# obc_flash.net
KiCad netlist of a schematic drawn in Altium Designer
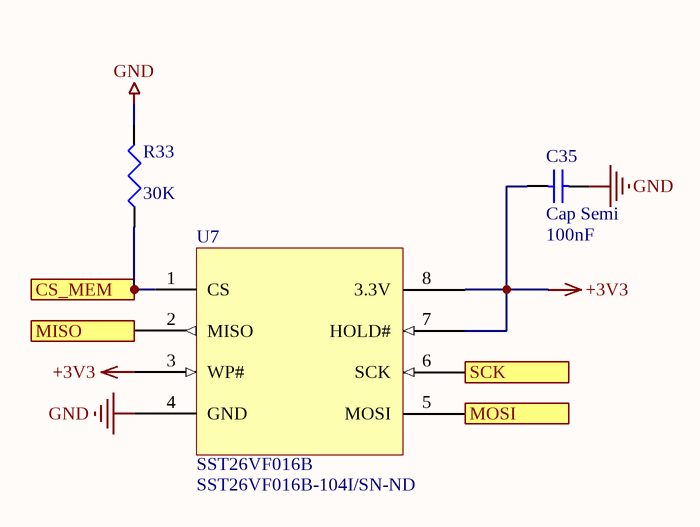
[diagram p0: obc_flash.SchDoc]

(export (version "E")
  (design (tool "Eeschema 10.0.6"))
  (components
    (comp (ref "C35")
      (value "Cap Semi")
      (footprint "1608[0603]")
      (description "Capacitor (Semiconductor SIM Model)")
      (fields (field (name "ALTIUM_VALUE") "100nF") (field (name "PUBLISHER") "Altium Limited"))
      (libsource (lib "Miscellaneous Devices") (part "Cap Semi"))
    )
    (comp (ref "R33")
      (value "30K")
      (footprint "J1-0603")
      (description "30K Pull-up resistor for RST. See page")
      (fields (field (name "PUBLISHER") "Altium Limited"))
      (libsource (lib "Miscellaneous Devices") (part "Res3"))
    )
    (comp (ref "U7")
      (value "SST26VF016B")
      (footprint "SOIC127P500X600-8N")
      (description "2.5V/3.0V 16 Mbit Serial Quad I/O (SQI) Flash Memory")
      (fields (field (name "SUPPLIER PART NUMBER 1") "SST26VF016B-104I/SN-ND"))
      (libsource (lib "heron-general") (part "SST26VF016B"))
    )
  )
  (nets
    (net (code "1") (name "+3V3") (class "Default")
      (node (ref "C35") (pin "1") (pinfunction "1_1") (pintype "passive"))
      (node (ref "U7") (pin "3") (pinfunction "WP#_3") (pintype "input"))
      (node (ref "U7") (pin "7") (pinfunction "HOLD#_7") (pintype "input"))
      (node (ref "U7") (pin "8") (pinfunction "3.3V_8") (pintype "power_in"))
    )
    (net (code "2") (name "/CS_MEM") (class "Default")
      (node (ref "R33") (pin "1") (pinfunction "1_1") (pintype "passive"))
      (node (ref "U7") (pin "1") (pinfunction "CS_1") (pintype "passive"))
    )
    (net (code "3") (name "/MISO") (class "Default")
      (node (ref "U7") (pin "2") (pinfunction "MISO_2") (pintype "output"))
    )
    (net (code "4") (name "/MOSI") (class "Default")
      (node (ref "U7") (pin "5") (pinfunction "MOSI_5") (pintype "passive"))
    )
    (net (code "5") (name "/SCK") (class "Default")
      (node (ref "U7") (pin "6") (pinfunction "SCK_6") (pintype "input"))
    )
    (net (code "6") (name "GND") (class "Default")
      (node (ref "C35") (pin "2") (pinfunction "2_2") (pintype "passive"))
      (node (ref "R33") (pin "2") (pinfunction "2_2") (pintype "passive"))
      (node (ref "U7") (pin "4") (pinfunction "GND_4") (pintype "power_in"))
    )
  )
)
